# STM32_Proto_Shield.net
KiCad netlist of a schematic drawn in EAGLE
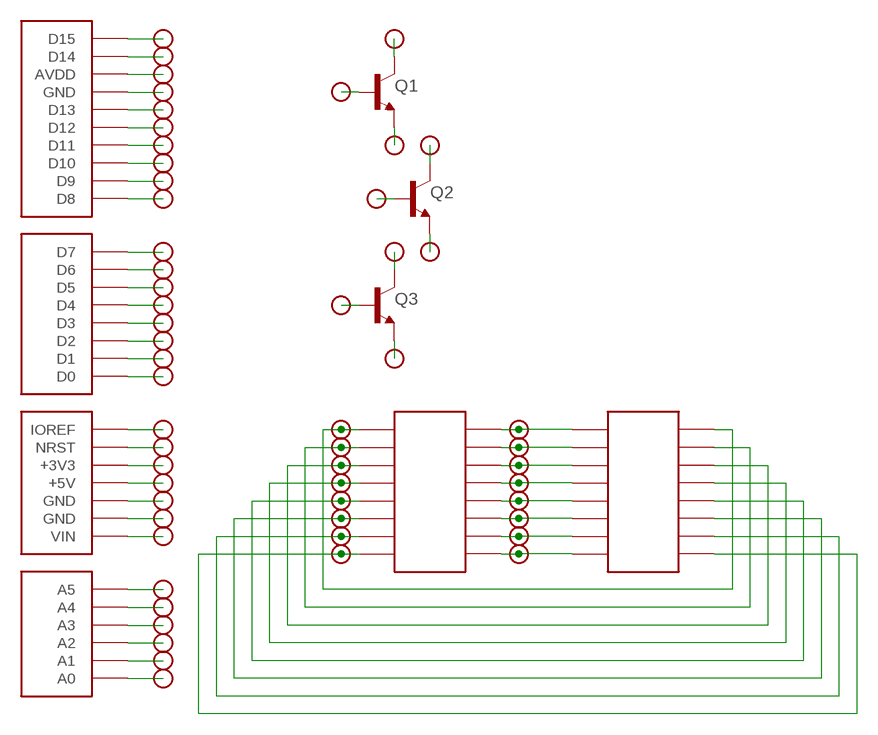
[diagram p0: schematic, sheet 1]

(export (version "E")
  (design (tool "Eeschema 10.0.6"))
  (components
    (comp (ref "J1")
      (value "DISCO_SHIELD_BARE")
      (footprint "eagle-import:DISCO_SHIELAD_BARE")
      (libsource (lib "eagle-import") (part "DISCO_SHIELD_BARE"))
    )
    (comp (ref "Q1")
      (value "BC817-40SMD")
      (footprint "eagle-import:SOT23-BEC")
      (libsource (lib "eagle-import") (part "BC817SMD-40"))
    )
    (comp (ref "Q2")
      (value "BC817-40SMD")
      (footprint "eagle-import:SOT23-BEC")
      (libsource (lib "eagle-import") (part "BC817SMD-40"))
    )
    (comp (ref "Q3")
      (value "BC817-40SMD")
      (footprint "eagle-import:SOT23-BEC")
      (libsource (lib "eagle-import") (part "BC817SMD-40"))
    )
    (comp (ref "U$1")
      (value "SOLDER_PAD")
      (footprint "eagle-import:1_08X19")
      (libsource (lib "eagle-import") (part "SOLDER_PAD"))
    )
    (comp (ref "U$2")
      (value "SOLDER_PAD")
      (footprint "eagle-import:1_08X19")
      (libsource (lib "eagle-import") (part "SOLDER_PAD"))
    )
    (comp (ref "U$3")
      (value "SOLDER_PAD")
      (footprint "eagle-import:1_08X19")
      (libsource (lib "eagle-import") (part "SOLDER_PAD"))
    )
    (comp (ref "U$4")
      (value "SOLDER_PAD")
      (footprint "eagle-import:1_08X19")
      (libsource (lib "eagle-import") (part "SOLDER_PAD"))
    )
    (comp (ref "U$5")
      (value "SOLDER_PAD")
      (footprint "eagle-import:1_08X19")
      (libsource (lib "eagle-import") (part "SOLDER_PAD"))
    )
    (comp (ref "U$6")
      (value "SOLDER_PAD")
      (footprint "eagle-import:1_08X19")
      (libsource (lib "eagle-import") (part "SOLDER_PAD"))
    )
    (comp (ref "U$7")
      (value "SOLDER_PAD")
      (footprint "eagle-import:1_08X19")
      (libsource (lib "eagle-import") (part "SOLDER_PAD"))
    )
    (comp (ref "U$8")
      (value "SOLDER_PAD")
      (footprint "eagle-import:1_08X19")
      (libsource (lib "eagle-import") (part "SOLDER_PAD"))
    )
    (comp (ref "U$9")
      (value "SOLDER_PAD")
      (footprint "eagle-import:1_08X19")
      (libsource (lib "eagle-import") (part "SOLDER_PAD"))
    )
    (comp (ref "U$10")
      (value "SOLDER_PAD")
      (footprint "eagle-import:1_08X19")
      (libsource (lib "eagle-import") (part "SOLDER_PAD"))
    )
    (comp (ref "U$11")
      (value "SOLDER_PAD")
      (footprint "eagle-import:1_08X19")
      (libsource (lib "eagle-import") (part "SOLDER_PAD"))
    )
    (comp (ref "U$12")
      (value "SOLDER_PAD")
      (footprint "eagle-import:1_08X19")
      (libsource (lib "eagle-import") (part "SOLDER_PAD"))
    )
    (comp (ref "U$13")
      (value "SOLDER_PAD")
      (footprint "eagle-import:1_08X19")
      (libsource (lib "eagle-import") (part "SOLDER_PAD"))
    )
    (comp (ref "U$14")
      (value "SOLDER_PAD")
      (footprint "eagle-import:1_08X19")
      (libsource (lib "eagle-import") (part "SOLDER_PAD"))
    )
    (comp (ref "U$15")
      (value "SOLDER_PAD")
      (footprint "eagle-import:1_08X19")
      (libsource (lib "eagle-import") (part "SOLDER_PAD"))
    )
    (comp (ref "U$16")
      (value "SOLDER_PAD")
      (footprint "eagle-import:1_08X19")
      (libsource (lib "eagle-import") (part "SOLDER_PAD"))
    )
    (comp (ref "U$17")
      (value "SOLDER_PAD")
      (footprint "eagle-import:1_08X19")
      (libsource (lib "eagle-import") (part "SOLDER_PAD"))
    )
    (comp (ref "U$18")
      (value "SOLDER_PAD")
      (footprint "eagle-import:1_08X19")
      (libsource (lib "eagle-import") (part "SOLDER_PAD"))
    )
    (comp (ref "U$19")
      (value "SOLDER_PAD")
      (footprint "eagle-import:1_08X19")
      (libsource (lib "eagle-import") (part "SOLDER_PAD"))
    )
    (comp (ref "U$20")
      (value "SOLDER_PAD")
      (footprint "eagle-import:1_08X19")
      (libsource (lib "eagle-import") (part "SOLDER_PAD"))
    )
    (comp (ref "U$21")
      (value "SOLDER_PAD")
      (footprint "eagle-import:1_08X19")
      (libsource (lib "eagle-import") (part "SOLDER_PAD"))
    )
    (comp (ref "U$22")
      (value "SOLDER_PAD")
      (footprint "eagle-import:1_08X19")
      (libsource (lib "eagle-import") (part "SOLDER_PAD"))
    )
    (comp (ref "U$23")
      (value "SOLDER_PAD")
      (footprint "eagle-import:1_08X19")
      (libsource (lib "eagle-import") (part "SOLDER_PAD"))
    )
    (comp (ref "U$24")
      (value "SOLDER_PAD")
      (footprint "eagle-import:1_08X19")
      (libsource (lib "eagle-import") (part "SOLDER_PAD"))
    )
    (comp (ref "U$25")
      (value "SOLDER_PAD")
      (footprint "eagle-import:1_08X19")
      (libsource (lib "eagle-import") (part "SOLDER_PAD"))
    )
    (comp (ref "U$26")
      (value "SOLDER_PAD")
      (footprint "eagle-import:1_08X19")
      (libsource (lib "eagle-import") (part "SOLDER_PAD"))
    )
    (comp (ref "U$27")
      (value "SOLDER_PAD")
      (footprint "eagle-import:1_08X19")
      (libsource (lib "eagle-import") (part "SOLDER_PAD"))
    )
    (comp (ref "U$28")
      (value "SOLDER_PAD")
      (footprint "eagle-import:1_08X19")
      (libsource (lib "eagle-import") (part "SOLDER_PAD"))
    )
    (comp (ref "U$29")
      (value "SOLDER_PAD")
      (footprint "eagle-import:1_08X19")
      (libsource (lib "eagle-import") (part "SOLDER_PAD"))
    )
    (comp (ref "U$30")
      (value "SOLDER_PAD")
      (footprint "eagle-import:1_08X19")
      (libsource (lib "eagle-import") (part "SOLDER_PAD"))
    )
    (comp (ref "U$31")
      (value "SOLDER_PAD")
      (footprint "eagle-import:1_08X19")
      (libsource (lib "eagle-import") (part "SOLDER_PAD"))
    )
    (comp (ref "U$32")
      (value "SOLDER_PAD")
      (footprint "eagle-import:1_08X19")
      (libsource (lib "eagle-import") (part "SOLDER_PAD"))
    )
    (comp (ref "U$33")
      (value "SOLDER_PAD")
      (footprint "eagle-import:1_08X19")
      (libsource (lib "eagle-import") (part "SOLDER_PAD"))
    )
    (comp (ref "U$34")
      (value "SOLDER_PAD")
      (footprint "eagle-import:1_08X19")
      (libsource (lib "eagle-import") (part "SOLDER_PAD"))
    )
    (comp (ref "U$35")
      (value "SOLDER_PAD")
      (footprint "eagle-import:1_08X19")
      (libsource (lib "eagle-import") (part "SOLDER_PAD"))
    )
    (comp (ref "U$36")
      (value "SOLDER_PAD")
      (footprint "eagle-import:1_08X19")
      (libsource (lib "eagle-import") (part "SOLDER_PAD"))
    )
    (comp (ref "U$37")
      (value "SOLDER_PAD")
      (footprint "eagle-import:1_08X19")
      (libsource (lib "eagle-import") (part "SOLDER_PAD"))
    )
    (comp (ref "U$38")
      (value "SOLDER_PAD")
      (footprint "eagle-import:1_08X19")
      (libsource (lib "eagle-import") (part "SOLDER_PAD"))
    )
    (comp (ref "U$39")
      (value "SOLDER_PAD")
      (footprint "eagle-import:1_08X19")
      (libsource (lib "eagle-import") (part "SOLDER_PAD"))
    )
    (comp (ref "U$40")
      (value "SOLDER_PAD")
      (footprint "eagle-import:1_08X19")
      (libsource (lib "eagle-import") (part "SOLDER_PAD"))
    )
    (comp (ref "U$41")
      (value "GENERIC_SMD_16")
      (footprint "eagle-import:16_TSOP_LONG")
      (libsource (lib "eagle-import") (part "GENERIC_SMD_16"))
    )
    (comp (ref "U$42")
      (value "SOLDER_PAD")
      (footprint "eagle-import:1_08X19")
      (libsource (lib "eagle-import") (part "SOLDER_PAD"))
    )
    (comp (ref "U$43")
      (value "SOLDER_PAD")
      (footprint "eagle-import:1_08X19")
      (libsource (lib "eagle-import") (part "SOLDER_PAD"))
    )
    (comp (ref "U$44")
      (value "SOLDER_PAD")
      (footprint "eagle-import:1_08X19")
      (libsource (lib "eagle-import") (part "SOLDER_PAD"))
    )
    (comp (ref "U$45")
      (value "SOLDER_PAD")
      (footprint "eagle-import:1_08X19")
      (libsource (lib "eagle-import") (part "SOLDER_PAD"))
    )
    (comp (ref "U$46")
      (value "SOLDER_PAD")
      (footprint "eagle-import:1_08X19")
      (libsource (lib "eagle-import") (part "SOLDER_PAD"))
    )
    (comp (ref "U$47")
      (value "SOLDER_PAD")
      (footprint "eagle-import:1_08X19")
      (libsource (lib "eagle-import") (part "SOLDER_PAD"))
    )
    (comp (ref "U$48")
      (value "SOLDER_PAD")
      (footprint "eagle-import:1_08X19")
      (libsource (lib "eagle-import") (part "SOLDER_PAD"))
    )
    (comp (ref "U$49")
      (value "SOLDER_PAD")
      (footprint "eagle-import:1_08X19")
      (libsource (lib "eagle-import") (part "SOLDER_PAD"))
    )
    (comp (ref "U$50")
      (value "SOLDER_PAD")
      (footprint "eagle-import:1_08X19")
      (libsource (lib "eagle-import") (part "SOLDER_PAD"))
    )
    (comp (ref "U$51")
      (value "SOLDER_PAD")
      (footprint "eagle-import:1_08X19")
      (libsource (lib "eagle-import") (part "SOLDER_PAD"))
    )
    (comp (ref "U$52")
      (value "SOLDER_PAD")
      (footprint "eagle-import:1_08X19")
      (libsource (lib "eagle-import") (part "SOLDER_PAD"))
    )
    (comp (ref "U$53")
      (value "SOLDER_PAD")
      (footprint "eagle-import:1_08X19")
      (libsource (lib "eagle-import") (part "SOLDER_PAD"))
    )
    (comp (ref "U$54")
      (value "SOLDER_PAD")
      (footprint "eagle-import:1_08X19")
      (libsource (lib "eagle-import") (part "SOLDER_PAD"))
    )
    (comp (ref "U$55")
      (value "SOLDER_PAD")
      (footprint "eagle-import:1_08X19")
      (libsource (lib "eagle-import") (part "SOLDER_PAD"))
    )
    (comp (ref "U$56")
      (value "SOLDER_PAD")
      (footprint "eagle-import:1_08X19")
      (libsource (lib "eagle-import") (part "SOLDER_PAD"))
    )
    (comp (ref "U$57")
      (value "SOLDER_PAD")
      (footprint "eagle-import:1_08X19")
      (libsource (lib "eagle-import") (part "SOLDER_PAD"))
    )
    (comp (ref "U$58")
      (value "GENERIC_SMD_16SOIC_LONG")
      (footprint "eagle-import:16_SOIC_LONG")
      (libsource (lib "eagle-import") (part "GENERIC_SMD_16SOIC_LONG"))
    )
  )
  (nets
    (net (code "1") (name "Net-(J1-PadA0)") (class "Default")
      (node (ref "J1") (pin "A0") (pinfunction "A0_A0") (pintype "bidirectional"))
      (node (ref "U$31") (pin "P$1") (pinfunction "P$1_P$1") (pintype "bidirectional"))
    )
    (net (code "2") (name "Net-(J1-PadA1)") (class "Default")
      (node (ref "J1") (pin "A1") (pinfunction "A1_A1") (pintype "bidirectional"))
      (node (ref "U$30") (pin "P$1") (pinfunction "P$1_P$1") (pintype "bidirectional"))
    )
    (net (code "3") (name "Net-(J1-PadA2)") (class "Default")
      (node (ref "J1") (pin "A2") (pinfunction "A2_A2") (pintype "bidirectional"))
      (node (ref "U$29") (pin "P$1") (pinfunction "P$1_P$1") (pintype "bidirectional"))
    )
    (net (code "4") (name "Net-(J1-PadA3)") (class "Default")
      (node (ref "J1") (pin "A3") (pinfunction "A3_A3") (pintype "bidirectional"))
      (node (ref "U$28") (pin "P$1") (pinfunction "P$1_P$1") (pintype "bidirectional"))
    )
    (net (code "5") (name "Net-(J1-PadA4)") (class "Default")
      (node (ref "J1") (pin "A4") (pinfunction "A4_A4") (pintype "bidirectional"))
      (node (ref "U$27") (pin "P$1") (pinfunction "P$1_P$1") (pintype "bidirectional"))
    )
    (net (code "6") (name "Net-(J1-PadA5)") (class "Default")
      (node (ref "J1") (pin "A5") (pinfunction "A5_A5") (pintype "bidirectional"))
      (node (ref "U$26") (pin "P$1") (pinfunction "P$1_P$1") (pintype "bidirectional"))
    )
    (net (code "7") (name "Net-(J1-PadAVDD)") (class "Default")
      (node (ref "J1") (pin "AVDD") (pinfunction "AVDD_AVDD") (pintype "bidirectional"))
      (node (ref "U$3") (pin "P$1") (pinfunction "P$1_P$1") (pintype "bidirectional"))
    )
    (net (code "8") (name "Net-(J1-PadD0)") (class "Default")
      (node (ref "J1") (pin "D0") (pinfunction "D0_D0") (pintype "bidirectional"))
      (node (ref "U$18") (pin "P$1") (pinfunction "P$1_P$1") (pintype "bidirectional"))
    )
    (net (code "9") (name "Net-(J1-PadD1)") (class "Default")
      (node (ref "J1") (pin "D1") (pinfunction "D1_D1") (pintype "bidirectional"))
      (node (ref "U$17") (pin "P$1") (pinfunction "P$1_P$1") (pintype "bidirectional"))
    )
    (net (code "10") (name "Net-(J1-PadD2)") (class "Default")
      (node (ref "J1") (pin "D2") (pinfunction "D2_D2") (pintype "bidirectional"))
      (node (ref "U$16") (pin "P$1") (pinfunction "P$1_P$1") (pintype "bidirectional"))
    )
    (net (code "11") (name "Net-(J1-PadD3)") (class "Default")
      (node (ref "J1") (pin "D3") (pinfunction "D3_D3") (pintype "bidirectional"))
      (node (ref "U$15") (pin "P$1") (pinfunction "P$1_P$1") (pintype "bidirectional"))
    )
    (net (code "12") (name "Net-(J1-PadD4)") (class "Default")
      (node (ref "J1") (pin "D4") (pinfunction "D4_D4") (pintype "bidirectional"))
      (node (ref "U$14") (pin "P$1") (pinfunction "P$1_P$1") (pintype "bidirectional"))
    )
    (net (code "13") (name "Net-(J1-PadD5)") (class "Default")
      (node (ref "J1") (pin "D5") (pinfunction "D5_D5") (pintype "bidirectional"))
      (node (ref "U$13") (pin "P$1") (pinfunction "P$1_P$1") (pintype "bidirectional"))
    )
    (net (code "14") (name "Net-(J1-PadD6)") (class "Default")
      (node (ref "J1") (pin "D6") (pinfunction "D6_D6") (pintype "bidirectional"))
      (node (ref "U$12") (pin "P$1") (pinfunction "P$1_P$1") (pintype "bidirectional"))
    )
    (net (code "15") (name "Net-(J1-PadD7)") (class "Default")
      (node (ref "J1") (pin "D7") (pinfunction "D7_D7") (pintype "bidirectional"))
      (node (ref "U$11") (pin "P$1") (pinfunction "P$1_P$1") (pintype "bidirectional"))
    )
    (net (code "16") (name "Net-(J1-PadD8)") (class "Default")
      (node (ref "J1") (pin "D8") (pinfunction "D8_D8") (pintype "bidirectional"))
      (node (ref "U$10") (pin "P$1") (pinfunction "P$1_P$1") (pintype "bidirectional"))
    )
    (net (code "17") (name "Net-(J1-PadD9)") (class "Default")
      (node (ref "J1") (pin "D9") (pinfunction "D9_D9") (pintype "bidirectional"))
      (node (ref "U$9") (pin "P$1") (pinfunction "P$1_P$1") (pintype "bidirectional"))
    )
    (net (code "18") (name "Net-(J1-PadD10)") (class "Default")
      (node (ref "J1") (pin "D10") (pinfunction "D10_D10") (pintype "bidirectional"))
      (node (ref "U$8") (pin "P$1") (pinfunction "P$1_P$1") (pintype "bidirectional"))
    )
    (net (code "19") (name "Net-(J1-PadD11)") (class "Default")
      (node (ref "J1") (pin "D11") (pinfunction "D11_D11") (pintype "bidirectional"))
      (node (ref "U$7") (pin "P$1") (pinfunction "P$1_P$1") (pintype "bidirectional"))
    )
    (net (code "20") (name "Net-(J1-PadD12)") (class "Default")
      (node (ref "J1") (pin "D12") (pinfunction "D12_D12") (pintype "bidirectional"))
      (node (ref "U$6") (pin "P$1") (pinfunction "P$1_P$1") (pintype "bidirectional"))
    )
    (net (code "21") (name "Net-(J1-PadD13)") (class "Default")
      (node (ref "J1") (pin "D13") (pinfunction "D13_D13") (pintype "bidirectional"))
      (node (ref "U$5") (pin "P$1") (pinfunction "P$1_P$1") (pintype "bidirectional"))
    )
    (net (code "22") (name "Net-(J1-PadD14)") (class "Default")
      (node (ref "J1") (pin "D14") (pinfunction "D14_D14") (pintype "bidirectional"))
      (node (ref "U$2") (pin "P$1") (pinfunction "P$1_P$1") (pintype "bidirectional"))
    )
    (net (code "23") (name "Net-(J1-PadD15)") (class "Default")
      (node (ref "J1") (pin "D15") (pinfunction "D15_D15") (pintype "bidirectional"))
      (node (ref "U$1") (pin "P$1") (pinfunction "P$1_P$1") (pintype "bidirectional"))
    )
    (net (code "24") (name "Net-(J1-PadIOREF)") (class "Default")
      (node (ref "J1") (pin "IOREF") (pinfunction "IOREF_IOREF") (pintype "bidirectional"))
      (node (ref "U$19") (pin "P$1") (pinfunction "P$1_P$1") (pintype "bidirectional"))
    )
    (net (code "25") (name "Net-(J1-PadVIN)") (class "Default")
      (node (ref "J1") (pin "VIN") (pinfunction "VIN_VIN") (pintype "bidirectional"))
      (node (ref "U$25") (pin "P$1") (pinfunction "P$1_P$1") (pintype "bidirectional"))
    )
    (net (code "26") (name "Net-(J1B-+3V3)") (class "Default")
      (node (ref "J1") (pin "3V3") (pinfunction "+3V3_3V3") (pintype "bidirectional"))
      (node (ref "U$21") (pin "P$1") (pinfunction "P$1_P$1") (pintype "bidirectional"))
    )
    (net (code "27") (name "Net-(J1B-+5V)") (class "Default")
      (node (ref "J1") (pin "5V") (pinfunction "+5V_5V") (pintype "bidirectional"))
      (node (ref "U$22") (pin "P$1") (pinfunction "P$1_P$1") (pintype "bidirectional"))
    )
    (net (code "28") (name "Net-(J1B-GND-PadGND@1)") (class "Default")
      (node (ref "J1") (pin "GND@1") (pinfunction "GND_GND@1") (pintype "bidirectional"))
      (node (ref "U$24") (pin "P$1") (pinfunction "P$1_P$1") (pintype "bidirectional"))
    )
    (net (code "29") (name "Net-(J1B-GND-PadGND@2)") (class "Default")
      (node (ref "J1") (pin "GND@2") (pinfunction "GND_GND@2") (pintype "bidirectional"))
      (node (ref "U$23") (pin "P$1") (pinfunction "P$1_P$1") (pintype "bidirectional"))
    )
    (net (code "30") (name "Net-(J1B-NRST)") (class "Default")
      (node (ref "J1") (pin "RST") (pinfunction "NRST_RST") (pintype "bidirectional"))
      (node (ref "U$20") (pin "P$1") (pinfunction "P$1_P$1") (pintype "bidirectional"))
    )
    (net (code "31") (name "Net-(J1D-GND)") (class "Default")
      (node (ref "J1") (pin "GND_D") (pinfunction "GND_GND_D") (pintype "bidirectional"))
      (node (ref "U$4") (pin "P$1") (pinfunction "P$1_P$1") (pintype "bidirectional"))
    )
    (net (code "32") (name "Net-(Q1-PadB)") (class "Default")
      (node (ref "Q1") (pin "B") (pinfunction "B_B") (pintype "passive"))
      (node (ref "U$33") (pin "P$1") (pinfunction "P$1_P$1") (pintype "bidirectional"))
    )
    (net (code "33") (name "Net-(Q1-PadC)") (class "Default")
      (node (ref "Q1") (pin "C") (pinfunction "C_C") (pintype "passive"))
      (node (ref "U$32") (pin "P$1") (pinfunction "P$1_P$1") (pintype "bidirectional"))
    )
    (net (code "34") (name "Net-(Q1-PadE)") (class "Default")
      (node (ref "Q1") (pin "E") (pinfunction "E_E") (pintype "passive"))
      (node (ref "U$34") (pin "P$1") (pinfunction "P$1_P$1") (pintype "bidirectional"))
    )
    (net (code "35") (name "Net-(Q2-PadB)") (class "Default")
      (node (ref "Q2") (pin "B") (pinfunction "B_B") (pintype "passive"))
      (node (ref "U$37") (pin "P$1") (pinfunction "P$1_P$1") (pintype "bidirectional"))
    )
    (net (code "36") (name "Net-(Q2-PadC)") (class "Default")
      (node (ref "Q2") (pin "C") (pinfunction "C_C") (pintype "passive"))
      (node (ref "U$35") (pin "P$1") (pinfunction "P$1_P$1") (pintype "bidirectional"))
    )
    (net (code "37") (name "Net-(Q2-PadE)") (class "Default")
      (node (ref "Q2") (pin "E") (pinfunction "E_E") (pintype "passive"))
      (node (ref "U$36") (pin "P$1") (pinfunction "P$1_P$1") (pintype "bidirectional"))
    )
    (net (code "38") (name "Net-(Q3-PadB)") (class "Default")
      (node (ref "Q3") (pin "B") (pinfunction "B_B") (pintype "passive"))
      (node (ref "U$40") (pin "P$1") (pinfunction "P$1_P$1") (pintype "bidirectional"))
    )
    (net (code "39") (name "Net-(Q3-PadC)") (class "Default")
      (node (ref "Q3") (pin "C") (pinfunction "C_C") (pintype "passive"))
      (node (ref "U$38") (pin "P$1") (pinfunction "P$1_P$1") (pintype "bidirectional"))
    )
    (net (code "40") (name "Net-(Q3-PadE)") (class "Default")
      (node (ref "Q3") (pin "E") (pinfunction "E_E") (pintype "passive"))
      (node (ref "U$39") (pin "P$1") (pinfunction "P$1_P$1") (pintype "bidirectional"))
    )
    (net (code "41") (name "Net-(U$41-PadP$1)") (class "Default")
      (node (ref "U$41") (pin "P$1") (pinfunction "P$1_P$1") (pintype "bidirectional"))
      (node (ref "U$42") (pin "P$1") (pinfunction "P$1_P$1") (pintype "bidirectional"))
      (node (ref "U$58") (pin "P$16") (pinfunction "P$16_P$16") (pintype "bidirectional"))
    )
    (net (code "42") (name "Net-(U$41-PadP$2)") (class "Default")
      (node (ref "U$41") (pin "P$2") (pinfunction "P$2_P$2") (pintype "bidirectional"))
      (node (ref "U$43") (pin "P$1") (pinfunction "P$1_P$1") (pintype "bidirectional"))
      (node (ref "U$58") (pin "P$15") (pinfunction "P$15_P$15") (pintype "bidirectional"))
    )
    (net (code "43") (name "Net-(U$41-PadP$3)") (class "Default")
      (node (ref "U$41") (pin "P$3") (pinfunction "P$3_P$3") (pintype "bidirectional"))
      (node (ref "U$44") (pin "P$1") (pinfunction "P$1_P$1") (pintype "bidirectional"))
      (node (ref "U$58") (pin "P$14") (pinfunction "P$14_P$14") (pintype "bidirectional"))
    )
    (net (code "44") (name "Net-(U$41-PadP$4)") (class "Default")
      (node (ref "U$41") (pin "P$4") (pinfunction "P$4_P$4") (pintype "bidirectional"))
      (node (ref "U$45") (pin "P$1") (pinfunction "P$1_P$1") (pintype "bidirectional"))
      (node (ref "U$58") (pin "P$13") (pinfunction "P$13_P$13") (pintype "bidirectional"))
    )
    (net (code "45") (name "Net-(U$41-PadP$5)") (class "Default")
      (node (ref "U$41") (pin "P$5") (pinfunction "P$5_P$5") (pintype "bidirectional"))
      (node (ref "U$46") (pin "P$1") (pinfunction "P$1_P$1") (pintype "bidirectional"))
      (node (ref "U$58") (pin "P$12") (pinfunction "P$12_P$12") (pintype "bidirectional"))
    )
    (net (code "46") (name "Net-(U$41-PadP$6)") (class "Default")
      (node (ref "U$41") (pin "P$6") (pinfunction "P$6_P$6") (pintype "bidirectional"))
      (node (ref "U$47") (pin "P$1") (pinfunction "P$1_P$1") (pintype "bidirectional"))
      (node (ref "U$58") (pin "P$11") (pinfunction "P$11_P$11") (pintype "bidirectional"))
    )
    (net (code "47") (name "Net-(U$41-PadP$7)") (class "Default")
      (node (ref "U$41") (pin "P$7") (pinfunction "P$7_P$7") (pintype "bidirectional"))
      (node (ref "U$49") (pin "P$1") (pinfunction "P$1_P$1") (pintype "bidirectional"))
      (node (ref "U$58") (pin "P$10") (pinfunction "P$10_P$10") (pintype "bidirectional"))
    )
    (net (code "48") (name "Net-(U$41-PadP$8)") (class "Default")
      (node (ref "U$41") (pin "P$8") (pinfunction "P$8_P$8") (pintype "bidirectional"))
      (node (ref "U$48") (pin "P$1") (pinfunction "P$1_P$1") (pintype "bidirectional"))
      (node (ref "U$58") (pin "P$9") (pinfunction "P$9_P$9") (pintype "bidirectional"))
    )
    (net (code "49") (name "Net-(U$41-PadP$9)") (class "Default")
      (node (ref "U$41") (pin "P$9") (pinfunction "P$9_P$9") (pintype "bidirectional"))
      (node (ref "U$50") (pin "P$1") (pinfunction "P$1_P$1") (pintype "bidirectional"))
      (node (ref "U$58") (pin "P$8") (pinfunction "P$8_P$8") (pintype "bidirectional"))
    )
    (net (code "50") (name "Net-(U$41-PadP$10)") (class "Default")
      (node (ref "U$41") (pin "P$10") (pinfunction "P$10_P$10") (pintype "bidirectional"))
      (node (ref "U$51") (pin "P$1") (pinfunction "P$1_P$1") (pintype "bidirectional"))
      (node (ref "U$58") (pin "P$7") (pinfunction "P$7_P$7") (pintype "bidirectional"))
    )
    (net (code "51") (name "Net-(U$41-PadP$11)") (class "Default")
      (node (ref "U$41") (pin "P$11") (pinfunction "P$11_P$11") (pintype "bidirectional"))
      (node (ref "U$52") (pin "P$1") (pinfunction "P$1_P$1") (pintype "bidirectional"))
      (node (ref "U$58") (pin "P$6") (pinfunction "P$6_P$6") (pintype "bidirectional"))
    )
    (net (code "52") (name "Net-(U$41-PadP$12)") (class "Default")
      (node (ref "U$41") (pin "P$12") (pinfunction "P$12_P$12") (pintype "bidirectional"))
      (node (ref "U$53") (pin "P$1") (pinfunction "P$1_P$1") (pintype "bidirectional"))
      (node (ref "U$58") (pin "P$5") (pinfunction "P$5_P$5") (pintype "bidirectional"))
    )
    (net (code "53") (name "Net-(U$41-PadP$13)") (class "Default")
      (node (ref "U$41") (pin "P$13") (pinfunction "P$13_P$13") (pintype "bidirectional"))
      (node (ref "U$54") (pin "P$1") (pinfunction "P$1_P$1") (pintype "bidirectional"))
      (node (ref "U$58") (pin "P$4") (pinfunction "P$4_P$4") (pintype "bidirectional"))
    )
    (net (code "54") (name "Net-(U$41-PadP$14)") (class "Default")
      (node (ref "U$41") (pin "P$14") (pinfunction "P$14_P$14") (pintype "bidirectional"))
      (node (ref "U$55") (pin "P$1") (pinfunction "P$1_P$1") (pintype "bidirectional"))
      (node (ref "U$58") (pin "P$3") (pinfunction "P$3_P$3") (pintype "bidirectional"))
    )
    (net (code "55") (name "Net-(U$41-PadP$15)") (class "Default")
      (node (ref "U$41") (pin "P$15") (pinfunction "P$15_P$15") (pintype "bidirectional"))
      (node (ref "U$56") (pin "P$1") (pinfunction "P$1_P$1") (pintype "bidirectional"))
      (node (ref "U$58") (pin "P$2") (pinfunction "P$2_P$2") (pintype "bidirectional"))
    )
    (net (code "56") (name "Net-(U$41-PadP$16)") (class "Default")
      (node (ref "U$41") (pin "P$16") (pinfunction "P$16_P$16") (pintype "bidirectional"))
      (node (ref "U$57") (pin "P$1") (pinfunction "P$1_P$1") (pintype "bidirectional"))
      (node (ref "U$58") (pin "P$1") (pinfunction "P$1_P$1") (pintype "bidirectional"))
    )
  )
)
